# clock_from_gps.net
KiCad netlist of a schematic drawn in EAGLE
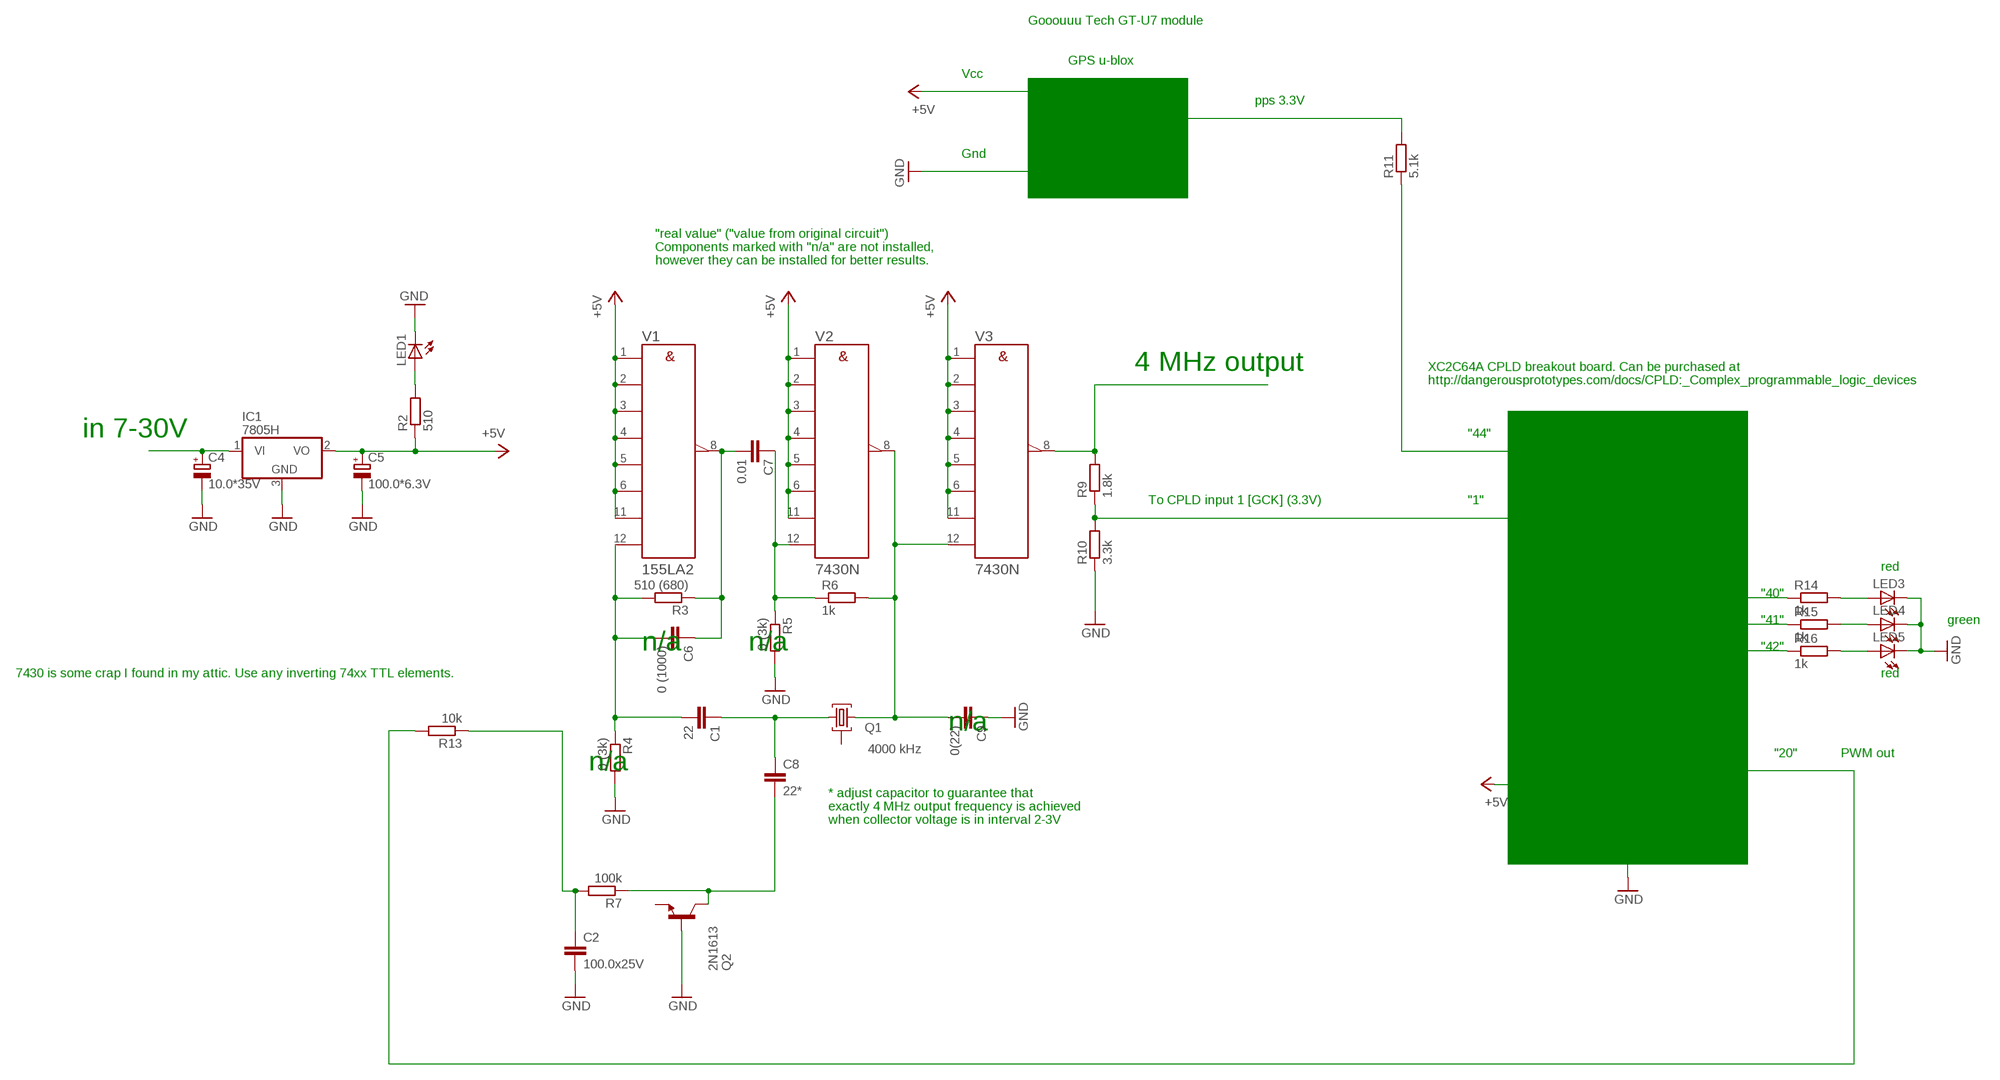
[diagram p0: schematic, sheet 1]

(export (version "E")
  (design (tool "Eeschema 10.0.6"))
  (components
    (comp (ref "C1")
      (value "22")
      (footprint "eagle-import:C025-024X044")
      (libsource (lib "eagle-import") (part "C-EU025-024X044"))
    )
    (comp (ref "C2")
      (value "100.0x25V")
      (footprint "eagle-import:C025-024X044")
      (libsource (lib "eagle-import") (part "C-EU025-024X044"))
    )
    (comp (ref "C4")
      (value "10.0*35V")
      (footprint "eagle-import:E5-4")
      (libsource (lib "eagle-import") (part "CPOL-EUE5-4"))
    )
    (comp (ref "C5")
      (value "100.0*6.3V")
      (footprint "eagle-import:E5-4")
      (libsource (lib "eagle-import") (part "CPOL-EUE5-4"))
    )
    (comp (ref "C6")
      (value "0 (1000)")
      (footprint "eagle-import:C025-024X044")
      (libsource (lib "eagle-import") (part "C-EU025-024X044"))
    )
    (comp (ref "C7")
      (value "0.01")
      (footprint "eagle-import:C025-024X044")
      (libsource (lib "eagle-import") (part "C-EU025-024X044"))
    )
    (comp (ref "C8")
      (value "22*")
      (footprint "eagle-import:C025-024X044")
      (libsource (lib "eagle-import") (part "C-EU025-024X044"))
    )
    (comp (ref "C9")
      (value "0(22)")
      (footprint "eagle-import:C025-024X044")
      (libsource (lib "eagle-import") (part "C-EU025-024X044"))
    )
    (comp (ref "IC1")
      (value "7805H")
      (footprint "eagle-import:TO39")
      (libsource (lib "eagle-import") (part "78H05"))
    )
    (comp (ref "LED1")
      (value "LED3MM")
      (footprint "eagle-import:LED3MM")
      (libsource (lib "eagle-import") (part "LED3MM"))
    )
    (comp (ref "LED3")
      (value "LED")
      (footprint "eagle-import:SMARTLED-TTW")
      (libsource (lib "eagle-import") (part "LED"))
    )
    (comp (ref "LED4")
      (value "LED")
      (footprint "eagle-import:SMARTLED-TTW")
      (libsource (lib "eagle-import") (part "LED"))
    )
    (comp (ref "LED5")
      (value "LED")
      (footprint "eagle-import:SMARTLED-TTW")
      (libsource (lib "eagle-import") (part "LED"))
    )
    (comp (ref "Q1")
      (value "4000 kHz")
      (footprint "eagle-import:HC49GW")
      (libsource (lib "eagle-import") (part "HC49GW"))
    )
    (comp (ref "Q2")
      (value "2N1613")
      (footprint "eagle-import:TO5")
      (libsource (lib "eagle-import") (part "2N1613"))
    )
    (comp (ref "R2")
      (value "510")
      (footprint "eagle-import:0204_5")
      (libsource (lib "eagle-import") (part "R-EU_0204/5"))
    )
    (comp (ref "R3")
      (value "510 (680)")
      (footprint "eagle-import:0204_5")
      (libsource (lib "eagle-import") (part "R-EU_0204/5"))
    )
    (comp (ref "R4")
      (value "0 (3k)")
      (footprint "eagle-import:0204_5")
      (libsource (lib "eagle-import") (part "R-EU_0204/5"))
    )
    (comp (ref "R5")
      (value "0 (3k)")
      (footprint "eagle-import:0204_5")
      (libsource (lib "eagle-import") (part "R-EU_0204/5"))
    )
    (comp (ref "R6")
      (value "1k")
      (footprint "eagle-import:0204_5")
      (libsource (lib "eagle-import") (part "R-EU_0204/5"))
    )
    (comp (ref "R7")
      (value "100k")
      (footprint "eagle-import:0204_5")
      (libsource (lib "eagle-import") (part "R-EU_0204/5"))
    )
    (comp (ref "R9")
      (value "1.8k")
      (footprint "eagle-import:0204_5")
      (libsource (lib "eagle-import") (part "R-EU_0204/5"))
    )
    (comp (ref "R10")
      (value "3.3k")
      (footprint "eagle-import:0204_5")
      (libsource (lib "eagle-import") (part "R-EU_0204/5"))
    )
    (comp (ref "R11")
      (value "5.1k")
      (footprint "eagle-import:0204_5")
      (libsource (lib "eagle-import") (part "R-EU_0204/5"))
    )
    (comp (ref "R13")
      (value "10k")
      (footprint "eagle-import:0204_5")
      (libsource (lib "eagle-import") (part "R-EU_0204/5"))
    )
    (comp (ref "R14")
      (value "1k")
      (footprint "eagle-import:0204_5")
      (libsource (lib "eagle-import") (part "R-EU_0204/5"))
    )
    (comp (ref "R15")
      (value "1k")
      (footprint "eagle-import:0204_5")
      (libsource (lib "eagle-import") (part "R-EU_0204/5"))
    )
    (comp (ref "R16")
      (value "1k")
      (footprint "eagle-import:0204_5")
      (libsource (lib "eagle-import") (part "R-EU_0204/5"))
    )
    (comp (ref "V1")
      (value "155LA2")
      (footprint "eagle-import:DIL14")
      (libsource (lib "eagle-import") (part "7430N"))
    )
    (comp (ref "V2")
      (value "7430N")
      (footprint "eagle-import:DIL14")
      (libsource (lib "eagle-import") (part "7430N"))
    )
    (comp (ref "V3")
      (value "7430N")
      (footprint "eagle-import:DIL14")
      (libsource (lib "eagle-import") (part "7430N"))
    )
  )
  (nets
    (net (code "1") (name "+5V") (class "Default")
      (node (ref "C5") (pin "+") (pinfunction "+_+") (pintype "passive"))
      (node (ref "IC1") (pin "2") (pinfunction "VO_2") (pintype "passive"))
      (node (ref "R2") (pin "1") (pinfunction "1_1") (pintype "passive"))
      (node (ref "V1") (pin "1") (pinfunction "A_1") (pintype "input"))
      (node (ref "V1") (pin "11") (pinfunction "G_11") (pintype "input"))
      (node (ref "V1") (pin "2") (pinfunction "B_2") (pintype "input"))
      (node (ref "V1") (pin "3") (pinfunction "C_3") (pintype "input"))
      (node (ref "V1") (pin "4") (pinfunction "D_4") (pintype "input"))
      (node (ref "V1") (pin "5") (pinfunction "E_5") (pintype "input"))
      (node (ref "V1") (pin "6") (pinfunction "F_6") (pintype "input"))
      (node (ref "V2") (pin "1") (pinfunction "A_1") (pintype "input"))
      (node (ref "V2") (pin "11") (pinfunction "G_11") (pintype "input"))
      (node (ref "V2") (pin "2") (pinfunction "B_2") (pintype "input"))
      (node (ref "V2") (pin "3") (pinfunction "C_3") (pintype "input"))
      (node (ref "V2") (pin "4") (pinfunction "D_4") (pintype "input"))
      (node (ref "V2") (pin "5") (pinfunction "E_5") (pintype "input"))
      (node (ref "V2") (pin "6") (pinfunction "F_6") (pintype "input"))
      (node (ref "V3") (pin "1") (pinfunction "A_1") (pintype "input"))
      (node (ref "V3") (pin "11") (pinfunction "G_11") (pintype "input"))
      (node (ref "V3") (pin "2") (pinfunction "B_2") (pintype "input"))
      (node (ref "V3") (pin "3") (pinfunction "C_3") (pintype "input"))
      (node (ref "V3") (pin "4") (pinfunction "D_4") (pintype "input"))
      (node (ref "V3") (pin "5") (pinfunction "E_5") (pintype "input"))
      (node (ref "V3") (pin "6") (pinfunction "F_6") (pintype "input"))
    )
    (net (code "2") (name "GND") (class "Default")
      (node (ref "C2") (pin "2") (pinfunction "2_2") (pintype "passive"))
      (node (ref "C4") (pin "-") (pinfunction "-_-") (pintype "passive"))
      (node (ref "C5") (pin "-") (pinfunction "-_-") (pintype "passive"))
      (node (ref "C9") (pin "1") (pinfunction "1_1") (pintype "passive"))
      (node (ref "IC1") (pin "3") (pinfunction "GND_3") (pintype "passive"))
      (node (ref "LED1") (pin "K") (pinfunction "C_K") (pintype "passive"))
      (node (ref "LED3") (pin "C@1") (pinfunction "C_C@1") (pintype "passive"))
      (node (ref "LED4") (pin "C@1") (pinfunction "C_C@1") (pintype "passive"))
      (node (ref "LED5") (pin "C@1") (pinfunction "C_C@1") (pintype "passive"))
      (node (ref "Q2") (pin "2") (pinfunction "B_2") (pintype "passive"))
      (node (ref "R10") (pin "1") (pinfunction "1_1") (pintype "passive"))
      (node (ref "R4") (pin "2") (pinfunction "2_2") (pintype "passive"))
      (node (ref "R5") (pin "2") (pinfunction "2_2") (pintype "passive"))
    )
    (net (code "3") (name "Net-(C1-Pad1)") (class "Default")
      (node (ref "C1") (pin "1") (pinfunction "1_1") (pintype "passive"))
      (node (ref "C8") (pin "1") (pinfunction "1_1") (pintype "passive"))
      (node (ref "Q1") (pin "2") (pinfunction "2_2") (pintype "passive"))
    )
    (net (code "4") (name "Net-(C2-Pad1)") (class "Default")
      (node (ref "C2") (pin "1") (pinfunction "1_1") (pintype "passive"))
      (node (ref "R13") (pin "1") (pinfunction "1_1") (pintype "passive"))
      (node (ref "R7") (pin "2") (pinfunction "2_2") (pintype "passive"))
    )
    (net (code "5") (name "Net-(IC1-VI)") (class "Default")
      (node (ref "C4") (pin "+") (pinfunction "+_+") (pintype "passive"))
      (node (ref "IC1") (pin "1") (pinfunction "VI_1") (pintype "input"))
    )
    (net (code "6") (name "Net-(LED1-PadA)") (class "Default")
      (node (ref "LED1") (pin "A") (pinfunction "A_A") (pintype "passive"))
      (node (ref "R2") (pin "2") (pinfunction "2_2") (pintype "passive"))
    )
    (net (code "7") (name "Net-(LED3-A)") (class "Default")
      (node (ref "LED3") (pin "A@1") (pinfunction "A_A@1") (pintype "passive"))
      (node (ref "R14") (pin "2") (pinfunction "2_2") (pintype "passive"))
    )
    (net (code "8") (name "Net-(LED4-A)") (class "Default")
      (node (ref "LED4") (pin "A@1") (pinfunction "A_A@1") (pintype "passive"))
      (node (ref "R15") (pin "2") (pinfunction "2_2") (pintype "passive"))
    )
    (net (code "9") (name "Net-(LED5-A)") (class "Default")
      (node (ref "LED5") (pin "A@1") (pinfunction "A_A@1") (pintype "passive"))
      (node (ref "R16") (pin "2") (pinfunction "2_2") (pintype "passive"))
    )
    (net (code "10") (name "Net-(Q2-C)") (class "Default")
      (node (ref "C8") (pin "2") (pinfunction "2_2") (pintype "passive"))
      (node (ref "Q2") (pin "3") (pinfunction "C_3") (pintype "passive"))
      (node (ref "R7") (pin "1") (pinfunction "1_1") (pintype "passive"))
    )
    (net (code "11") (name "Net-(R10-Pad2)") (class "Default")
      (node (ref "R10") (pin "2") (pinfunction "2_2") (pintype "passive"))
      (node (ref "R9") (pin "1") (pinfunction "1_1") (pintype "passive"))
    )
    (net (code "12") (name "Net-(V1C-H)") (class "Default")
      (node (ref "C1") (pin "2") (pinfunction "2_2") (pintype "passive"))
      (node (ref "C6") (pin "2") (pinfunction "2_2") (pintype "passive"))
      (node (ref "R3") (pin "2") (pinfunction "2_2") (pintype "passive"))
      (node (ref "R4") (pin "1") (pinfunction "1_1") (pintype "passive"))
      (node (ref "V1") (pin "12") (pinfunction "H_12") (pintype "input"))
    )
    (net (code "13") (name "Net-(V1C-Y)") (class "Default")
      (node (ref "C6") (pin "1") (pinfunction "1_1") (pintype "passive"))
      (node (ref "C7") (pin "2") (pinfunction "2_2") (pintype "passive"))
      (node (ref "R3") (pin "1") (pinfunction "1_1") (pintype "passive"))
      (node (ref "V1") (pin "8") (pinfunction "Y_8") (pintype "output"))
    )
    (net (code "14") (name "Net-(V2C-H)") (class "Default")
      (node (ref "C7") (pin "1") (pinfunction "1_1") (pintype "passive"))
      (node (ref "R5") (pin "1") (pinfunction "1_1") (pintype "passive"))
      (node (ref "R6") (pin "1") (pinfunction "1_1") (pintype "passive"))
      (node (ref "V2") (pin "12") (pinfunction "H_12") (pintype "input"))
    )
    (net (code "15") (name "Net-(V2C-Y)") (class "Default")
      (node (ref "C9") (pin "2") (pinfunction "2_2") (pintype "passive"))
      (node (ref "Q1") (pin "1") (pinfunction "1_1") (pintype "passive"))
      (node (ref "R6") (pin "2") (pinfunction "2_2") (pintype "passive"))
      (node (ref "V2") (pin "8") (pinfunction "Y_8") (pintype "output"))
      (node (ref "V3") (pin "12") (pinfunction "H_12") (pintype "input"))
    )
    (net (code "16") (name "Net-(V3C-Y)") (class "Default")
      (node (ref "R9") (pin "2") (pinfunction "2_2") (pintype "passive"))
      (node (ref "V3") (pin "8") (pinfunction "Y_8") (pintype "output"))
    )
    (net (code "17") (name "unconnected-(Q1-Pad3)") (class "Default")
      (node (ref "Q1") (pin "3") (pinfunction "3_3") (pintype "passive"))
    )
    (net (code "18") (name "unconnected-(Q2-E-Pad1)") (class "Default")
      (node (ref "Q2") (pin "1") (pinfunction "E_1") (pintype "passive"))
    )
    (net (code "19") (name "unconnected-(R11-Pad1)") (class "Default")
      (node (ref "R11") (pin "1") (pinfunction "1_1") (pintype "passive"))
    )
    (net (code "20") (name "unconnected-(R11-Pad2)") (class "Default")
      (node (ref "R11") (pin "2") (pinfunction "2_2") (pintype "passive"))
    )
    (net (code "21") (name "unconnected-(R13-Pad2)") (class "Default")
      (node (ref "R13") (pin "2") (pinfunction "2_2") (pintype "passive"))
    )
    (net (code "22") (name "unconnected-(R14-Pad1)") (class "Default")
      (node (ref "R14") (pin "1") (pinfunction "1_1") (pintype "passive"))
    )
    (net (code "23") (name "unconnected-(R15-Pad1)") (class "Default")
      (node (ref "R15") (pin "1") (pinfunction "1_1") (pintype "passive"))
    )
    (net (code "24") (name "unconnected-(R16-Pad1)") (class "Default")
      (node (ref "R16") (pin "1") (pinfunction "1_1") (pintype "passive"))
    )
  )
)
